# GR_Alim.net
KiCad netlist of a schematic drawn in Altium Designer
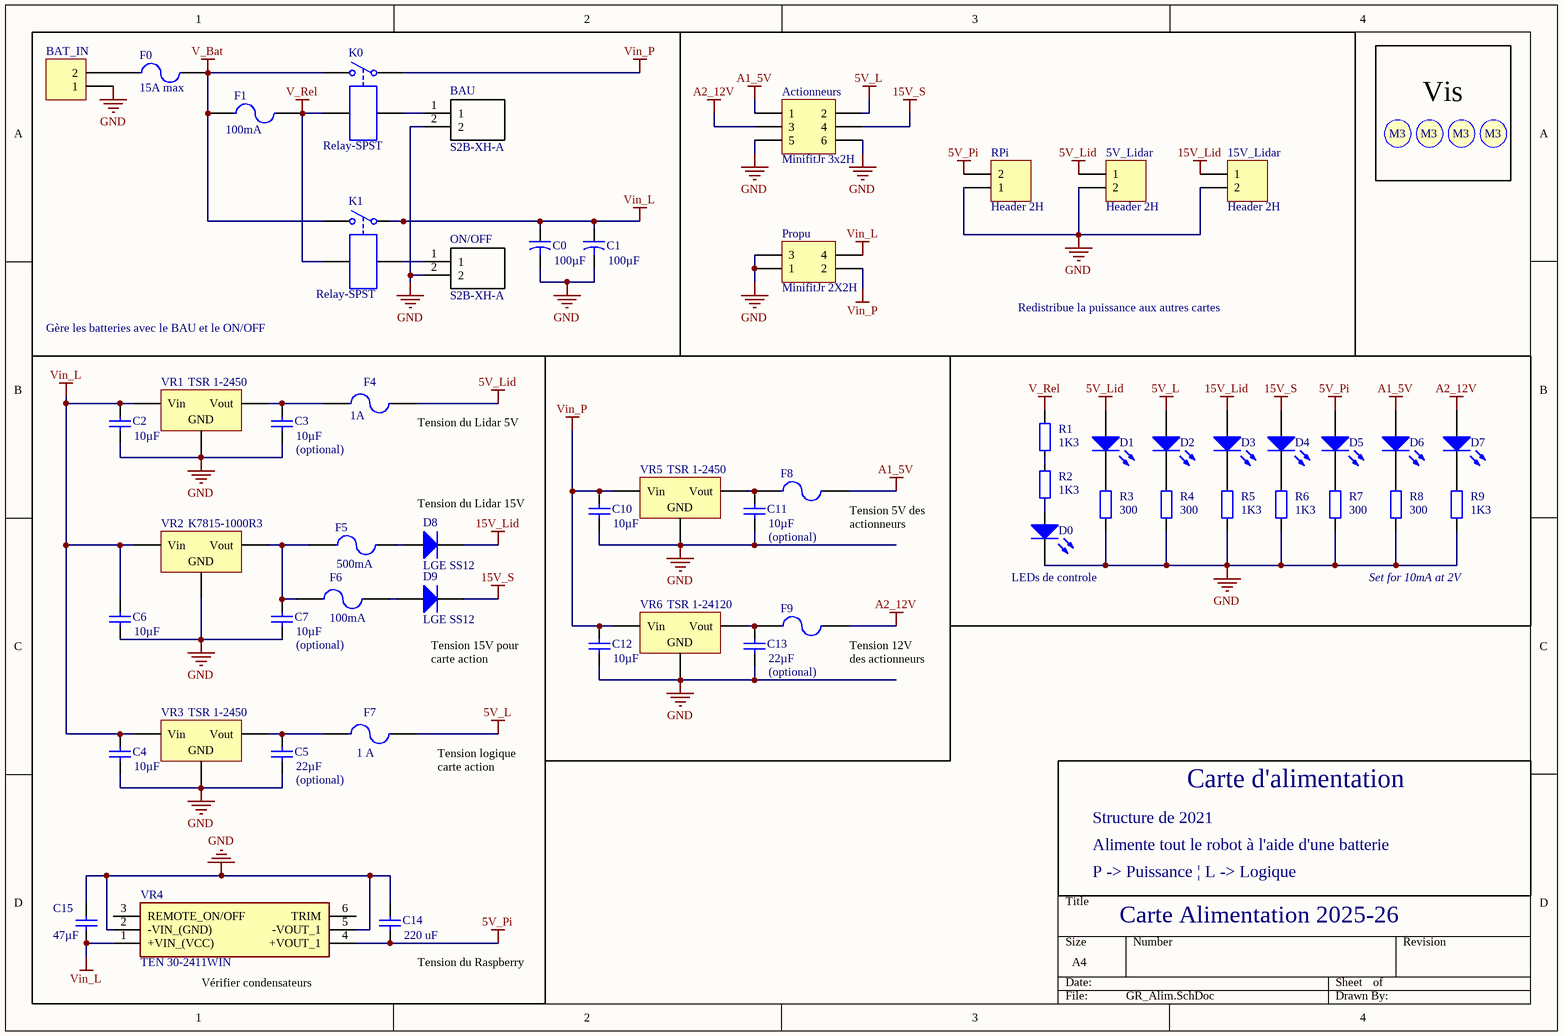
[diagram p0: GR_Alim.SchDoc]

(export (version "E")
  (design (tool "Eeschema 10.0.6"))
  (components
    (comp (ref "5V_Lidar")
      (value "Header 2H")
      (footprint "S2B-XH-A")
      (description "Header, 2-Pin, Right Angle")
      (fields (field (name "PUBLISHER") "Altium Limited"))
      (libsource (lib "Miscellaneous Connectors") (part "Header 2H"))
    )
    (comp (ref "15V_Lidar")
      (value "Header 2H")
      (footprint "S2B-XH-A")
      (description "Header, 2-Pin, Right Angle")
      (fields (field (name "PUBLISHER") "Altium Limited"))
      (libsource (lib "Miscellaneous Connectors") (part "Header 2H"))
    )
    (comp (ref "Actionneurs")
      (value "MinifitJr 3x2H")
      (footprint "MOLEX_MINIFITJR_3X2")
      (description "Header, 3-Pin, Dual row, Right Angle")
      (fields (field (name "PUBLISHER") "Altium Limited"))
      (libsource (lib "Miscellaneous Connectors") (part "Header 3X2H"))
    )
    (comp (ref "BAT_IN")
      (value "Battery Onboard Solder")
      (footprint "Battery SALE")
      (description "Header, 2-Pin\r\nBattery Onboard Solder\r\n24V")
      (fields (field (name "PUBLISHER") "Altium Limited"))
      (libsource (lib "Miscellaneous Connectors") (part "Header 2"))
    )
    (comp (ref "BAU")
      (value "S2B-XH-A")
      (footprint "S2B-XH-A")
      (description "Connector")
      (fields (field (name "MANUFACTURER_PART_NUMBER") "S2B-XH-A-1(LF)(SN)"))
      (libsource (lib "SamacSys") (part "S2B-XH-A-1_LF__SN_"))
    )
    (comp (ref "C0")
      (value "100µF")
      (footprint "Condensateur")
      (description "Capacitor")
      (fields (field (name "Comment") "Cap2") (field (name "PUBLISHER") "Altium Limited"))
      (libsource (lib "Miscellaneous Devices") (part "Cap2"))
    )
    (comp (ref "C1")
      (value "100µF")
      (footprint "Condensateur")
      (description "Capacitor")
      (fields (field (name "Comment") "Cap2") (field (name "PUBLISHER") "Altium Limited"))
      (libsource (lib "Miscellaneous Devices") (part "Cap2"))
    )
    (comp (ref "C2")
      (value "10µF")
      (footprint "Capacitor 1206")
      (description "Capacitor")
      (fields (field (name "Comment") "Cap") (field (name "PUBLISHER") "Altium Limited"))
      (libsource (lib "Miscellaneous Devices") (part "Cap"))
    )
    (comp (ref "C3")
      (value "(optional)")
      (footprint "Capacitor 1206")
      (description "Capacitor")
      (fields (field (name "ALTIUM_VALUE") "10µF") (field (name "PUBLISHER") "Altium Limited"))
      (libsource (lib "Miscellaneous Devices") (part "Cap"))
    )
    (comp (ref "C4")
      (value "10µF")
      (footprint "Capacitor 1206")
      (description "Capacitor")
      (fields (field (name "Comment") "Cap") (field (name "PUBLISHER") "Altium Limited"))
      (libsource (lib "Miscellaneous Devices") (part "Cap"))
    )
    (comp (ref "C5")
      (value "(optional)")
      (footprint "Capacitor 1206")
      (description "Capacitor")
      (fields (field (name "ALTIUM_VALUE") "22µF") (field (name "PUBLISHER") "Altium Limited"))
      (libsource (lib "Miscellaneous Devices") (part "Cap"))
    )
    (comp (ref "C6")
      (value "10µF")
      (footprint "Capacitor 1206")
      (description "Capacitor")
      (fields (field (name "Comment") "Cap") (field (name "PUBLISHER") "Altium Limited"))
      (libsource (lib "Miscellaneous Devices") (part "Cap"))
    )
    (comp (ref "C7")
      (value "(optional)")
      (footprint "Capacitor 1206")
      (description "Capacitor")
      (fields (field (name "ALTIUM_VALUE") "10µF") (field (name "PUBLISHER") "Altium Limited"))
      (libsource (lib "Miscellaneous Devices") (part "Cap"))
    )
    (comp (ref "C10")
      (value "10µF")
      (footprint "Capacitor 1206")
      (description "Capacitor")
      (fields (field (name "Comment") "Cap") (field (name "PUBLISHER") "Altium Limited"))
      (libsource (lib "Miscellaneous Devices") (part "Cap"))
    )
    (comp (ref "C11")
      (value "(optional)")
      (footprint "Capacitor 1206")
      (description "Capacitor")
      (fields (field (name "ALTIUM_VALUE") "10µF") (field (name "PUBLISHER") "Altium Limited"))
      (libsource (lib "Miscellaneous Devices") (part "Cap"))
    )
    (comp (ref "C12")
      (value "10µF")
      (footprint "Capacitor 1206")
      (description "Capacitor")
      (fields (field (name "Comment") "Cap") (field (name "PUBLISHER") "Altium Limited"))
      (libsource (lib "Miscellaneous Devices") (part "Cap"))
    )
    (comp (ref "C13")
      (value "(optional)")
      (footprint "Capacitor 1206")
      (description "Capacitor")
      (fields (field (name "ALTIUM_VALUE") "22µF") (field (name "PUBLISHER") "Altium Limited"))
      (libsource (lib "Miscellaneous Devices") (part "Cap"))
    )
    (comp (ref "C14")
      (value "220 uF")
      (footprint "Capacitor 1206")
      (description "Capacitor")
      (fields (field (name "Comment") "Cap") (field (name "PUBLISHER") "Altium Limited"))
      (libsource (lib "Miscellaneous Devices") (part "Cap"))
    )
    (comp (ref "C15")
      (value "47µF")
      (footprint "Capacitor 1206")
      (description "Capacitor")
      (fields (field (name "Comment") "Cap") (field (name "PUBLISHER") "Altium Limited"))
      (libsource (lib "Miscellaneous Devices") (part "Cap"))
    )
    (comp (ref "D0")
      (value "V_Rel")
      (footprint "KP-3216SEC")
      (description "Typical RED, GREEN, YELLOW, AMBER GaAs LED")
      (fields (field (name "PUBLISHER") "Altium Limited"))
      (libsource (lib "Miscellaneous Devices") (part "LED2"))
    )
    (comp (ref "D1")
      (value "5V_L")
      (footprint "KP-3216SEC")
      (description "Typical RED, GREEN, YELLOW, AMBER GaAs LED")
      (fields (field (name "PUBLISHER") "Altium Limited"))
      (libsource (lib "Miscellaneous Devices") (part "LED2"))
    )
    (comp (ref "D2")
      (value "5V_Lid")
      (footprint "KP-3216SEC")
      (description "Typical RED, GREEN, YELLOW, AMBER GaAs LED")
      (fields (field (name "PUBLISHER") "Altium Limited"))
      (libsource (lib "Miscellaneous Devices") (part "LED2"))
    )
    (comp (ref "D3")
      (value "A_2")
      (footprint "KP-3216SEC")
      (description "Typical RED, GREEN, YELLOW, AMBER GaAs LED")
      (fields (field (name "PUBLISHER") "Altium Limited"))
      (libsource (lib "Miscellaneous Devices") (part "LED2"))
    )
    (comp (ref "D4")
      (value "5V_L")
      (footprint "KP-3216SEC")
      (description "Typical RED, GREEN, YELLOW, AMBER GaAs LED")
      (fields (field (name "PUBLISHER") "Altium Limited"))
      (libsource (lib "Miscellaneous Devices") (part "LED2"))
    )
    (comp (ref "D5")
      (value "5V_L")
      (footprint "KP-3216SEC")
      (description "Typical RED, GREEN, YELLOW, AMBER GaAs LED")
      (fields (field (name "PUBLISHER") "Altium Limited"))
      (libsource (lib "Miscellaneous Devices") (part "LED2"))
    )
    (comp (ref "D6")
      (value "A_1")
      (footprint "KP-3216SEC")
      (description "Typical RED, GREEN, YELLOW, AMBER GaAs LED")
      (fields (field (name "PUBLISHER") "Altium Limited"))
      (libsource (lib "Miscellaneous Devices") (part "LED2"))
    )
    (comp (ref "D7")
      (value "A_2_12V")
      (footprint "KP-3216SEC")
      (description "Typical RED, GREEN, YELLOW, AMBER GaAs LED")
      (fields (field (name "PUBLISHER") "Altium Limited"))
      (libsource (lib "Miscellaneous Devices") (part "LED2"))
    )
    (comp (ref "D8")
      (value "LGE SS12")
      (footprint "SMB")
      (description "Default Diode")
      (fields (field (name "PUBLISHER") "Altium Limited"))
      (libsource (lib "Miscellaneous Devices") (part "Diode"))
    )
    (comp (ref "D9")
      (value "LGE SS12")
      (footprint "SMB")
      (description "Default Diode")
      (fields (field (name "PUBLISHER") "Altium Limited"))
      (libsource (lib "Miscellaneous Devices") (part "Diode"))
    )
    (comp (ref "F0")
      (value "15A max")
      (footprint "Fuse")
      (description "Main Fuse")
      (fields (field (name "PUBLISHER") "Altium Limited"))
      (libsource (lib "Miscellaneous Devices") (part "Fuse 2"))
    )
    (comp (ref "F1")
      (value "100mA")
      (footprint "3.5X2.8X1.9")
      (description "Resettable fuse T0")
      (fields (field (name "PUBLISHER") "Altium Limited"))
      (libsource (lib "Miscellaneous Devices") (part "Fuse 2"))
    )
    (comp (ref "F4")
      (value "1A")
      (footprint "3.5X2.8X1.9")
      (description "Resettable Fuse αA / JF")
      (fields (field (name "PUBLISHER") "Altium Limited"))
      (libsource (lib "Miscellaneous Devices") (part "Fuse 2"))
    )
    (comp (ref "F5")
      (value "500mA")
      (footprint "3.5X2.8X1.9")
      (description "Resettable Fuse αA / JF")
      (fields (field (name "PUBLISHER") "Altium Limited"))
      (libsource (lib "Miscellaneous Devices") (part "Fuse 2"))
    )
    (comp (ref "F6")
      (value "100mA")
      (footprint "3.5X2.8X1.9")
      (description "Resettable Fuse T0")
      (fields (field (name "PUBLISHER") "Altium Limited"))
      (libsource (lib "Miscellaneous Devices") (part "Fuse 2"))
    )
    (comp (ref "F7")
      (value "1 A")
      (footprint "3.5X2.8X1.9")
      (description "Resettable fuse JG / BF")
      (fields (field (name "PUBLISHER") "Altium Limited"))
      (libsource (lib "Miscellaneous Devices") (part "Fuse 2"))
    )
    (comp (ref "F8")
      (value "Fuse 2")
      (footprint "3.5X2.8X1.9")
      (description "Résistance 0Ω")
      (fields (field (name "PUBLISHER") "Altium Limited"))
      (libsource (lib "Miscellaneous Devices") (part "Fuse 2"))
    )
    (comp (ref "F9")
      (value "Fuse 2")
      (footprint "3.5X2.8X1.9")
      (description "Résistance 0Ω")
      (fields (field (name "PUBLISHER") "Altium Limited"))
      (libsource (lib "Miscellaneous Devices") (part "Fuse 2"))
    )
    (comp (ref "K0")
      (value "Relay-SPST")
      (footprint "Relay")
      (description "Single-Pole Single-Throw Relay")
      (fields (field (name "PUBLISHER") "Altium Limited"))
      (libsource (lib "Miscellaneous Devices") (part "Relay-SPST"))
    )
    (comp (ref "K1")
      (value "Relay-SPST")
      (footprint "Relay")
      (description "Single-Pole Single-Throw Relay")
      (fields (field (name "PUBLISHER") "Altium Limited"))
      (libsource (lib "Miscellaneous Devices") (part "Relay-SPST"))
    )
    (comp (ref "ON/OFF")
      (value "S2B-XH-A")
      (footprint "S2B-XH-A")
      (description "Connector")
      (fields (field (name "MANUFACTURER_PART_NUMBER") "S2B-XH-A-1(LF)(SN)"))
      (libsource (lib "SamacSys") (part "S2B-XH-A-1_LF__SN_"))
    )
    (comp (ref "Propu")
      (value "MinifitJr 2X2H")
      (footprint "MOLEX_MINIFITJR_2X2H")
      (description "Header, 2-Pin, Dual row, Right Angle")
      (fields (field (name "PUBLISHER") "Altium Limited"))
      (libsource (lib "Miscellaneous Connectors") (part "Header 2X2H"))
    )
    (comp (ref "R1")
      (value "1K3")
      (footprint "Resistor 1206")
      (description "Resistor")
      (fields (field (name "Comment") "Res2") (field (name "PUBLISHER") "Altium Limited"))
      (libsource (lib "Miscellaneous Devices") (part "Res2"))
    )
    (comp (ref "R2")
      (value "1K3")
      (footprint "Resistor 1206")
      (description "Resistor")
      (fields (field (name "Comment") "Res2") (field (name "PUBLISHER") "Altium Limited"))
      (libsource (lib "Miscellaneous Devices") (part "Res2"))
    )
    (comp (ref "R3")
      (value "300")
      (footprint "Resistor 1206")
      (description "Resistor")
      (fields (field (name "Comment") "Res2") (field (name "PUBLISHER") "Altium Limited"))
      (libsource (lib "") (part "Res2_1"))
    )
    (comp (ref "R4")
      (value "300")
      (footprint "Resistor 1206")
      (description "Resistor")
      (fields (field (name "Comment") "Res2") (field (name "PUBLISHER") "Altium Limited"))
      (libsource (lib "") (part "Res2_1"))
    )
    (comp (ref "R5")
      (value "1K3")
      (footprint "Resistor 1206")
      (description "Resistor")
      (fields (field (name "Comment") "Res2") (field (name "PUBLISHER") "Altium Limited"))
      (libsource (lib "Miscellaneous Devices") (part "Res2"))
    )
    (comp (ref "R6")
      (value "1K3")
      (footprint "Resistor 1206")
      (description "Resistor")
      (fields (field (name "Comment") "Res2") (field (name "PUBLISHER") "Altium Limited"))
      (libsource (lib "Miscellaneous Devices") (part "Res2"))
    )
    (comp (ref "R7")
      (value "300")
      (footprint "Resistor 1206")
      (description "Resistor")
      (fields (field (name "Comment") "Res2") (field (name "PUBLISHER") "Altium Limited"))
      (libsource (lib "Miscellaneous Devices") (part "Res2"))
    )
    (comp (ref "R8")
      (value "300")
      (footprint "Resistor 1206")
      (description "Resistor")
      (fields (field (name "PUBLISHER") "Altium Limited"))
      (libsource (lib "Miscellaneous Devices") (part "Res2"))
    )
    (comp (ref "R9")
      (value "1K3")
      (footprint "Resistor 1206")
      (description "Resistor")
      (fields (field (name "PUBLISHER") "Altium Limited"))
      (libsource (lib "Miscellaneous Devices") (part "Res2"))
    )
    (comp (ref "RPi")
      (value "Header 2H")
      (footprint "Molex_MiniFitJr_2x1H")
      (description "Header, 2-Pin, Right Angle")
      (fields (field (name "PUBLISHER") "Altium Limited"))
      (libsource (lib "") (part "Header 2H_1"))
    )
    (comp (ref "S1")
      (value "Screw M3")
      (footprint "Screw M3")
      (libsource (lib "Robot_2019") (part "Screw M3"))
    )
    (comp (ref "S2")
      (value "Screw M3")
      (footprint "Screw M3")
      (libsource (lib "Robot_2019") (part "Screw M3"))
    )
    (comp (ref "S3")
      (value "Screw M3")
      (footprint "Screw M3")
      (libsource (lib "Robot_2019") (part "Screw M3"))
    )
    (comp (ref "S4")
      (value "Screw M3")
      (footprint "Screw M3")
      (libsource (lib "Robot_2019") (part "Screw M3"))
    )
    (comp (ref "VR1")
      (value "TSR 1-2450")
      (footprint "TRS")
      (description "Voltage Regulator")
      (fields (field (name "PUBLISHER") "Altium Limited"))
      (libsource (lib "Miscellaneous Devices") (part "Volt Reg"))
    )
    (comp (ref "VR2")
      (value "K7815-1000R3")
      (footprint "TRS")
      (description "Voltage Regulator")
      (fields (field (name "PUBLISHER") "Altium Limited"))
      (libsource (lib "Miscellaneous Devices") (part "Volt Reg"))
    )
    (comp (ref "VR3")
      (value "TSR 1-2450")
      (footprint "TRS")
      (description "Voltage Regulator")
      (fields (field (name "PUBLISHER") "Altium Limited"))
      (libsource (lib "Miscellaneous Devices") (part "Volt Reg"))
    )
    (comp (ref "VR4")
      (value "TEN 30-2411WIN")
      (footprint "Robot_2020:TEN302411WIN")
      (description "Power Supply")
      (fields (field (name "MOUSER PART NUMBER") "495-TEN-30-2411WIN"))
      (libsource (lib "*") (part "TEN_30-2411WIN"))
    )
    (comp (ref "VR5")
      (value "TSR 1-2450")
      (footprint "TRS")
      (description "Voltage Regulator")
      (fields (field (name "PUBLISHER") "Altium Limited"))
      (libsource (lib "Miscellaneous Devices") (part "Volt Reg"))
    )
    (comp (ref "VR6")
      (value "TSR 1-24120")
      (footprint "TRS")
      (description "Voltage Regulator")
      (fields (field (name "PUBLISHER") "Altium Limited"))
      (libsource (lib "Miscellaneous Devices") (part "Volt Reg"))
    )
  )
  (nets
    (net (code "1") (name "5V_L") (class "Default")
      (node (ref "Actionneurs") (pin "2") (pinfunction "2_2") (pintype "passive"))
      (node (ref "D2") (pin "1") (pinfunction "A_1") (pintype "passive"))
      (node (ref "F7") (pin "2") (pinfunction "2_2") (pintype "passive"))
    )
    (net (code "2") (name "5V_Lid") (class "Default")
      (node (ref "5V_Lidar") (pin "1") (pinfunction "1_1") (pintype "passive"))
      (node (ref "D1") (pin "1") (pinfunction "A_1") (pintype "passive"))
      (node (ref "F4") (pin "2") (pinfunction "2_2") (pintype "passive"))
    )
    (net (code "3") (name "5V_Pi") (class "Default")
      (node (ref "C14") (pin "1") (pinfunction "1_1") (pintype "passive"))
      (node (ref "D5") (pin "1") (pinfunction "A_1") (pintype "passive"))
      (node (ref "RPi") (pin "2") (pinfunction "2_2") (pintype "passive"))
      (node (ref "VR4") (pin "4") (pinfunction "+VOUT_1_4") (pintype "passive"))
    )
    (net (code "4") (name "15V_Lid") (class "Default")
      (node (ref "15V_Lidar") (pin "1") (pinfunction "1_1") (pintype "passive"))
      (node (ref "D3") (pin "1") (pinfunction "A_1") (pintype "passive"))
      (node (ref "D8") (pin "2") (pinfunction "K_2") (pintype "passive"))
    )
    (net (code "5") (name "15V_S") (class "Default")
      (node (ref "Actionneurs") (pin "4") (pinfunction "4_4") (pintype "passive"))
      (node (ref "D4") (pin "1") (pinfunction "A_1") (pintype "passive"))
      (node (ref "D9") (pin "2") (pinfunction "K_2") (pintype "passive"))
    )
    (net (code "6") (name "A1_5V") (class "Default")
      (node (ref "Actionneurs") (pin "1") (pinfunction "1_1") (pintype "passive"))
      (node (ref "D6") (pin "1") (pinfunction "A_1") (pintype "passive"))
      (node (ref "F8") (pin "2") (pinfunction "2_2") (pintype "passive"))
    )
    (net (code "7") (name "A2_12V") (class "Default")
      (node (ref "Actionneurs") (pin "3") (pinfunction "3_3") (pintype "passive"))
      (node (ref "D7") (pin "1") (pinfunction "A_1") (pintype "passive"))
      (node (ref "F9") (pin "2") (pinfunction "2_2") (pintype "passive"))
    )
    (net (code "8") (name "GND") (class "Default")
      (node (ref "15V_Lidar") (pin "2") (pinfunction "2_2") (pintype "passive"))
      (node (ref "5V_Lidar") (pin "2") (pinfunction "2_2") (pintype "passive"))
      (node (ref "Actionneurs") (pin "5") (pinfunction "5_5") (pintype "passive"))
      (node (ref "Actionneurs") (pin "6") (pinfunction "6_6") (pintype "passive"))
      (node (ref "BAT_IN") (pin "1") (pinfunction "1_1") (pintype "passive"))
      (node (ref "BAU") (pin "2") (pinfunction "2_2") (pintype "passive"))
      (node (ref "C0") (pin "2") (pinfunction "2_2") (pintype "passive"))
      (node (ref "C1") (pin "2") (pinfunction "2_2") (pintype "passive"))
      (node (ref "C10") (pin "1") (pinfunction "1_1") (pintype "passive"))
      (node (ref "C11") (pin "1") (pinfunction "1_1") (pintype "passive"))
      (node (ref "C12") (pin "1") (pinfunction "1_1") (pintype "passive"))
      (node (ref "C13") (pin "1") (pinfunction "1_1") (pintype "passive"))
      (node (ref "C14") (pin "2") (pinfunction "2_2") (pintype "passive"))
      (node (ref "C15") (pin "2") (pinfunction "2_2") (pintype "passive"))
      (node (ref "C2") (pin "1") (pinfunction "1_1") (pintype "passive"))
      (node (ref "C3") (pin "1") (pinfunction "1_1") (pintype "passive"))
      (node (ref "C4") (pin "1") (pinfunction "1_1") (pintype "passive"))
      (node (ref "C5") (pin "1") (pinfunction "1_1") (pintype "passive"))
      (node (ref "C6") (pin "1") (pinfunction "1_1") (pintype "passive"))
      (node (ref "C7") (pin "1") (pinfunction "1_1") (pintype "passive"))
      (node (ref "D0") (pin "2") (pinfunction "K_2") (pintype "passive"))
      (node (ref "ON/OFF") (pin "2") (pinfunction "2_2") (pintype "passive"))
      (node (ref "Propu") (pin "1") (pinfunction "1_1") (pintype "passive"))
      (node (ref "Propu") (pin "3") (pinfunction "3_3") (pintype "passive"))
      (node (ref "R3") (pin "1") (pinfunction "1_1") (pintype "passive"))
      (node (ref "R4") (pin "1") (pinfunction "1_1") (pintype "passive"))
      (node (ref "R5") (pin "2") (pinfunction "2_2") (pintype "passive"))
      (node (ref "R6") (pin "2") (pinfunction "2_2") (pintype "passive"))
      (node (ref "R7") (pin "2") (pinfunction "2_2") (pintype "passive"))
      (node (ref "R8") (pin "2") (pinfunction "2_2") (pintype "passive"))
      (node (ref "R9") (pin "2") (pinfunction "2_2") (pintype "passive"))
      (node (ref "RPi") (pin "1") (pinfunction "1_1") (pintype "passive"))
      (node (ref "VR1") (pin "2") (pinfunction "GND_2") (pintype "passive"))
      (node (ref "VR2") (pin "2") (pinfunction "GND_2") (pintype "passive"))
      (node (ref "VR3") (pin "2") (pinfunction "GND_2") (pintype "passive"))
      (node (ref "VR4") (pin "2") (pinfunction "-VIN_(GND)_2") (pintype "passive"))
      (node (ref "VR4") (pin "5") (pinfunction "-VOUT_1_5") (pintype "passive"))
      (node (ref "VR5") (pin "2") (pinfunction "GND_2") (pintype "passive"))
      (node (ref "VR6") (pin "2") (pinfunction "GND_2") (pintype "passive"))
    )
    (net (code "9") (name "Net-(BAT_IN-Pad2)") (class "Default")
      (node (ref "BAT_IN") (pin "2") (pinfunction "2_2") (pintype "passive"))
      (node (ref "F0") (pin "1") (pinfunction "1_1") (pintype "passive"))
    )
    (net (code "10") (name "Net-(BAU-Pad1)") (class "Default")
      (node (ref "BAU") (pin "1") (pinfunction "1_1") (pintype "passive"))
      (node (ref "K0") (pin "3") (pinfunction "3_3") (pintype "passive"))
    )
    (net (code "11") (name "Net-(D0-A)") (class "Default")
      (node (ref "D0") (pin "1") (pinfunction "A_1") (pintype "passive"))
      (node (ref "R2") (pin "2") (pinfunction "2_2") (pintype "passive"))
    )
    (net (code "12") (name "Net-(D1-K)") (class "Default")
      (node (ref "D1") (pin "2") (pinfunction "K_2") (pintype "passive"))
      (node (ref "R3") (pin "2") (pinfunction "2_2") (pintype "passive"))
    )
    (net (code "13") (name "Net-(D2-K)") (class "Default")
      (node (ref "D2") (pin "2") (pinfunction "K_2") (pintype "passive"))
      (node (ref "R4") (pin "2") (pinfunction "2_2") (pintype "passive"))
    )
    (net (code "14") (name "Net-(D3-K)") (class "Default")
      (node (ref "D3") (pin "2") (pinfunction "K_2") (pintype "passive"))
      (node (ref "R5") (pin "1") (pinfunction "1_1") (pintype "passive"))
    )
    (net (code "15") (name "Net-(D4-K)") (class "Default")
      (node (ref "D4") (pin "2") (pinfunction "K_2") (pintype "passive"))
      (node (ref "R6") (pin "1") (pinfunction "1_1") (pintype "passive"))
    )
    (net (code "16") (name "Net-(D5-K)") (class "Default")
      (node (ref "D5") (pin "2") (pinfunction "K_2") (pintype "passive"))
      (node (ref "R7") (pin "1") (pinfunction "1_1") (pintype "passive"))
    )
    (net (code "17") (name "Net-(D6-K)") (class "Default")
      (node (ref "D6") (pin "2") (pinfunction "K_2") (pintype "passive"))
      (node (ref "R8") (pin "1") (pinfunction "1_1") (pintype "passive"))
    )
    (net (code "18") (name "Net-(D7-K)") (class "Default")
      (node (ref "D7") (pin "2") (pinfunction "K_2") (pintype "passive"))
      (node (ref "R9") (pin "1") (pinfunction "1_1") (pintype "passive"))
    )
    (net (code "19") (name "Net-(D8-A)") (class "Default")
      (node (ref "D8") (pin "1") (pinfunction "A_1") (pintype "passive"))
      (node (ref "F5") (pin "2") (pinfunction "2_2") (pintype "passive"))
    )
    (net (code "20") (name "Net-(D9-A)") (class "Default")
      (node (ref "D9") (pin "1") (pinfunction "A_1") (pintype "passive"))
      (node (ref "F6") (pin "2") (pinfunction "2_2") (pintype "passive"))
    )
    (net (code "21") (name "Net-(K1-Pad3)") (class "Default")
      (node (ref "K1") (pin "3") (pinfunction "3_3") (pintype "passive"))
      (node (ref "ON/OFF") (pin "1") (pinfunction "1_1") (pintype "passive"))
    )
    (net (code "22") (name "Net-(R1-Pad2)") (class "Default")
      (node (ref "R1") (pin "2") (pinfunction "2_2") (pintype "passive"))
      (node (ref "R2") (pin "1") (pinfunction "1_1") (pintype "passive"))
    )
    (net (code "23") (name "Net-(VR1-Vout)") (class "Default")
      (node (ref "C3") (pin "2") (pinfunction "2_2") (pintype "passive"))
      (node (ref "F4") (pin "1") (pinfunction "1_1") (pintype "passive"))
      (node (ref "VR1") (pin "3") (pinfunction "Vout_3") (pintype "passive"))
    )
    (net (code "24") (name "Net-(VR2-Vout)") (class "Default")
      (node (ref "C7") (pin "2") (pinfunction "2_2") (pintype "passive"))
      (node (ref "F5") (pin "1") (pinfunction "1_1") (pintype "passive"))
      (node (ref "F6") (pin "1") (pinfunction "1_1") (pintype "passive"))
      (node (ref "VR2") (pin "3") (pinfunction "Vout_3") (pintype "passive"))
    )
    (net (code "25") (name "Net-(VR3-Vout)") (class "Default")
      (node (ref "C5") (pin "2") (pinfunction "2_2") (pintype "passive"))
      (node (ref "F7") (pin "1") (pinfunction "1_1") (pintype "passive"))
      (node (ref "VR3") (pin "3") (pinfunction "Vout_3") (pintype "passive"))
    )
    (net (code "26") (name "Net-(VR5-Vout)") (class "Default")
      (node (ref "C11") (pin "2") (pinfunction "2_2") (pintype "passive"))
      (node (ref "F8") (pin "1") (pinfunction "1_1") (pintype "passive"))
      (node (ref "VR5") (pin "3") (pinfunction "Vout_3") (pintype "passive"))
    )
    (net (code "27") (name "Net-(VR6-Vout)") (class "Default")
      (node (ref "C13") (pin "2") (pinfunction "2_2") (pintype "passive"))
      (node (ref "F9") (pin "1") (pinfunction "1_1") (pintype "passive"))
      (node (ref "VR6") (pin "3") (pinfunction "Vout_3") (pintype "passive"))
    )
    (net (code "28") (name "V_Bat") (class "Default")
      (node (ref "F0") (pin "2") (pinfunction "2_2") (pintype "passive"))
      (node (ref "F1") (pin "1") (pinfunction "1_1") (pintype "passive"))
      (node (ref "K0") (pin "2") (pinfunction "2_2") (pintype "passive"))
      (node (ref "K1") (pin "2") (pinfunction "2_2") (pintype "passive"))
    )
    (net (code "29") (name "V_Rel") (class "Default")
      (node (ref "F1") (pin "2") (pinfunction "2_2") (pintype "passive"))
      (node (ref "K0") (pin "4") (pinfunction "4_4") (pintype "passive"))
      (node (ref "K1") (pin "4") (pinfunction "4_4") (pintype "passive"))
      (node (ref "R1") (pin "1") (pinfunction "1_1") (pintype "passive"))
    )
    (net (code "30") (name "Vin_L") (class "Default")
      (node (ref "C0") (pin "1") (pinfunction "1_1") (pintype "passive"))
      (node (ref "C1") (pin "1") (pinfunction "1_1") (pintype "passive"))
      (node (ref "C15") (pin "1") (pinfunction "1_1") (pintype "passive"))
      (node (ref "C2") (pin "2") (pinfunction "2_2") (pintype "passive"))
      (node (ref "C4") (pin "2") (pinfunction "2_2") (pintype "passive"))
      (node (ref "C6") (pin "2") (pinfunction "2_2") (pintype "passive"))
      (node (ref "K1") (pin "1") (pinfunction "1_1") (pintype "passive"))
      (node (ref "Propu") (pin "4") (pinfunction "4_4") (pintype "passive"))
      (node (ref "VR1") (pin "1") (pinfunction "Vin_1") (pintype "passive"))
      (node (ref "VR2") (pin "1") (pinfunction "Vin_1") (pintype "passive"))
      (node (ref "VR3") (pin "1") (pinfunction "Vin_1") (pintype "passive"))
      (node (ref "VR4") (pin "1") (pinfunction "+VIN_(VCC)_1") (pintype "passive"))
    )
    (net (code "31") (name "Vin_P") (class "Default")
      (node (ref "C10") (pin "2") (pinfunction "2_2") (pintype "passive"))
      (node (ref "C12") (pin "2") (pinfunction "2_2") (pintype "passive"))
      (node (ref "K0") (pin "1") (pinfunction "1_1") (pintype "passive"))
      (node (ref "Propu") (pin "2") (pinfunction "2_2") (pintype "passive"))
      (node (ref "VR5") (pin "1") (pinfunction "Vin_1") (pintype "passive"))
      (node (ref "VR6") (pin "1") (pinfunction "Vin_1") (pintype "passive"))
    )
    (net (code "32") (name "unconnected-(VR4-REMOTE_ON{slash}OFF-Pad3)") (class "Default")
      (node (ref "VR4") (pin "3") (pinfunction "REMOTE_ON/OFF_3") (pintype "passive"))
    )
    (net (code "33") (name "unconnected-(VR4-TRIM-Pad6)") (class "Default")
      (node (ref "VR4") (pin "6") (pinfunction "TRIM_6") (pintype "passive"))
    )
  )
)
